# Step_Driver.net
KiCad netlist of a schematic drawn in Altium Designer
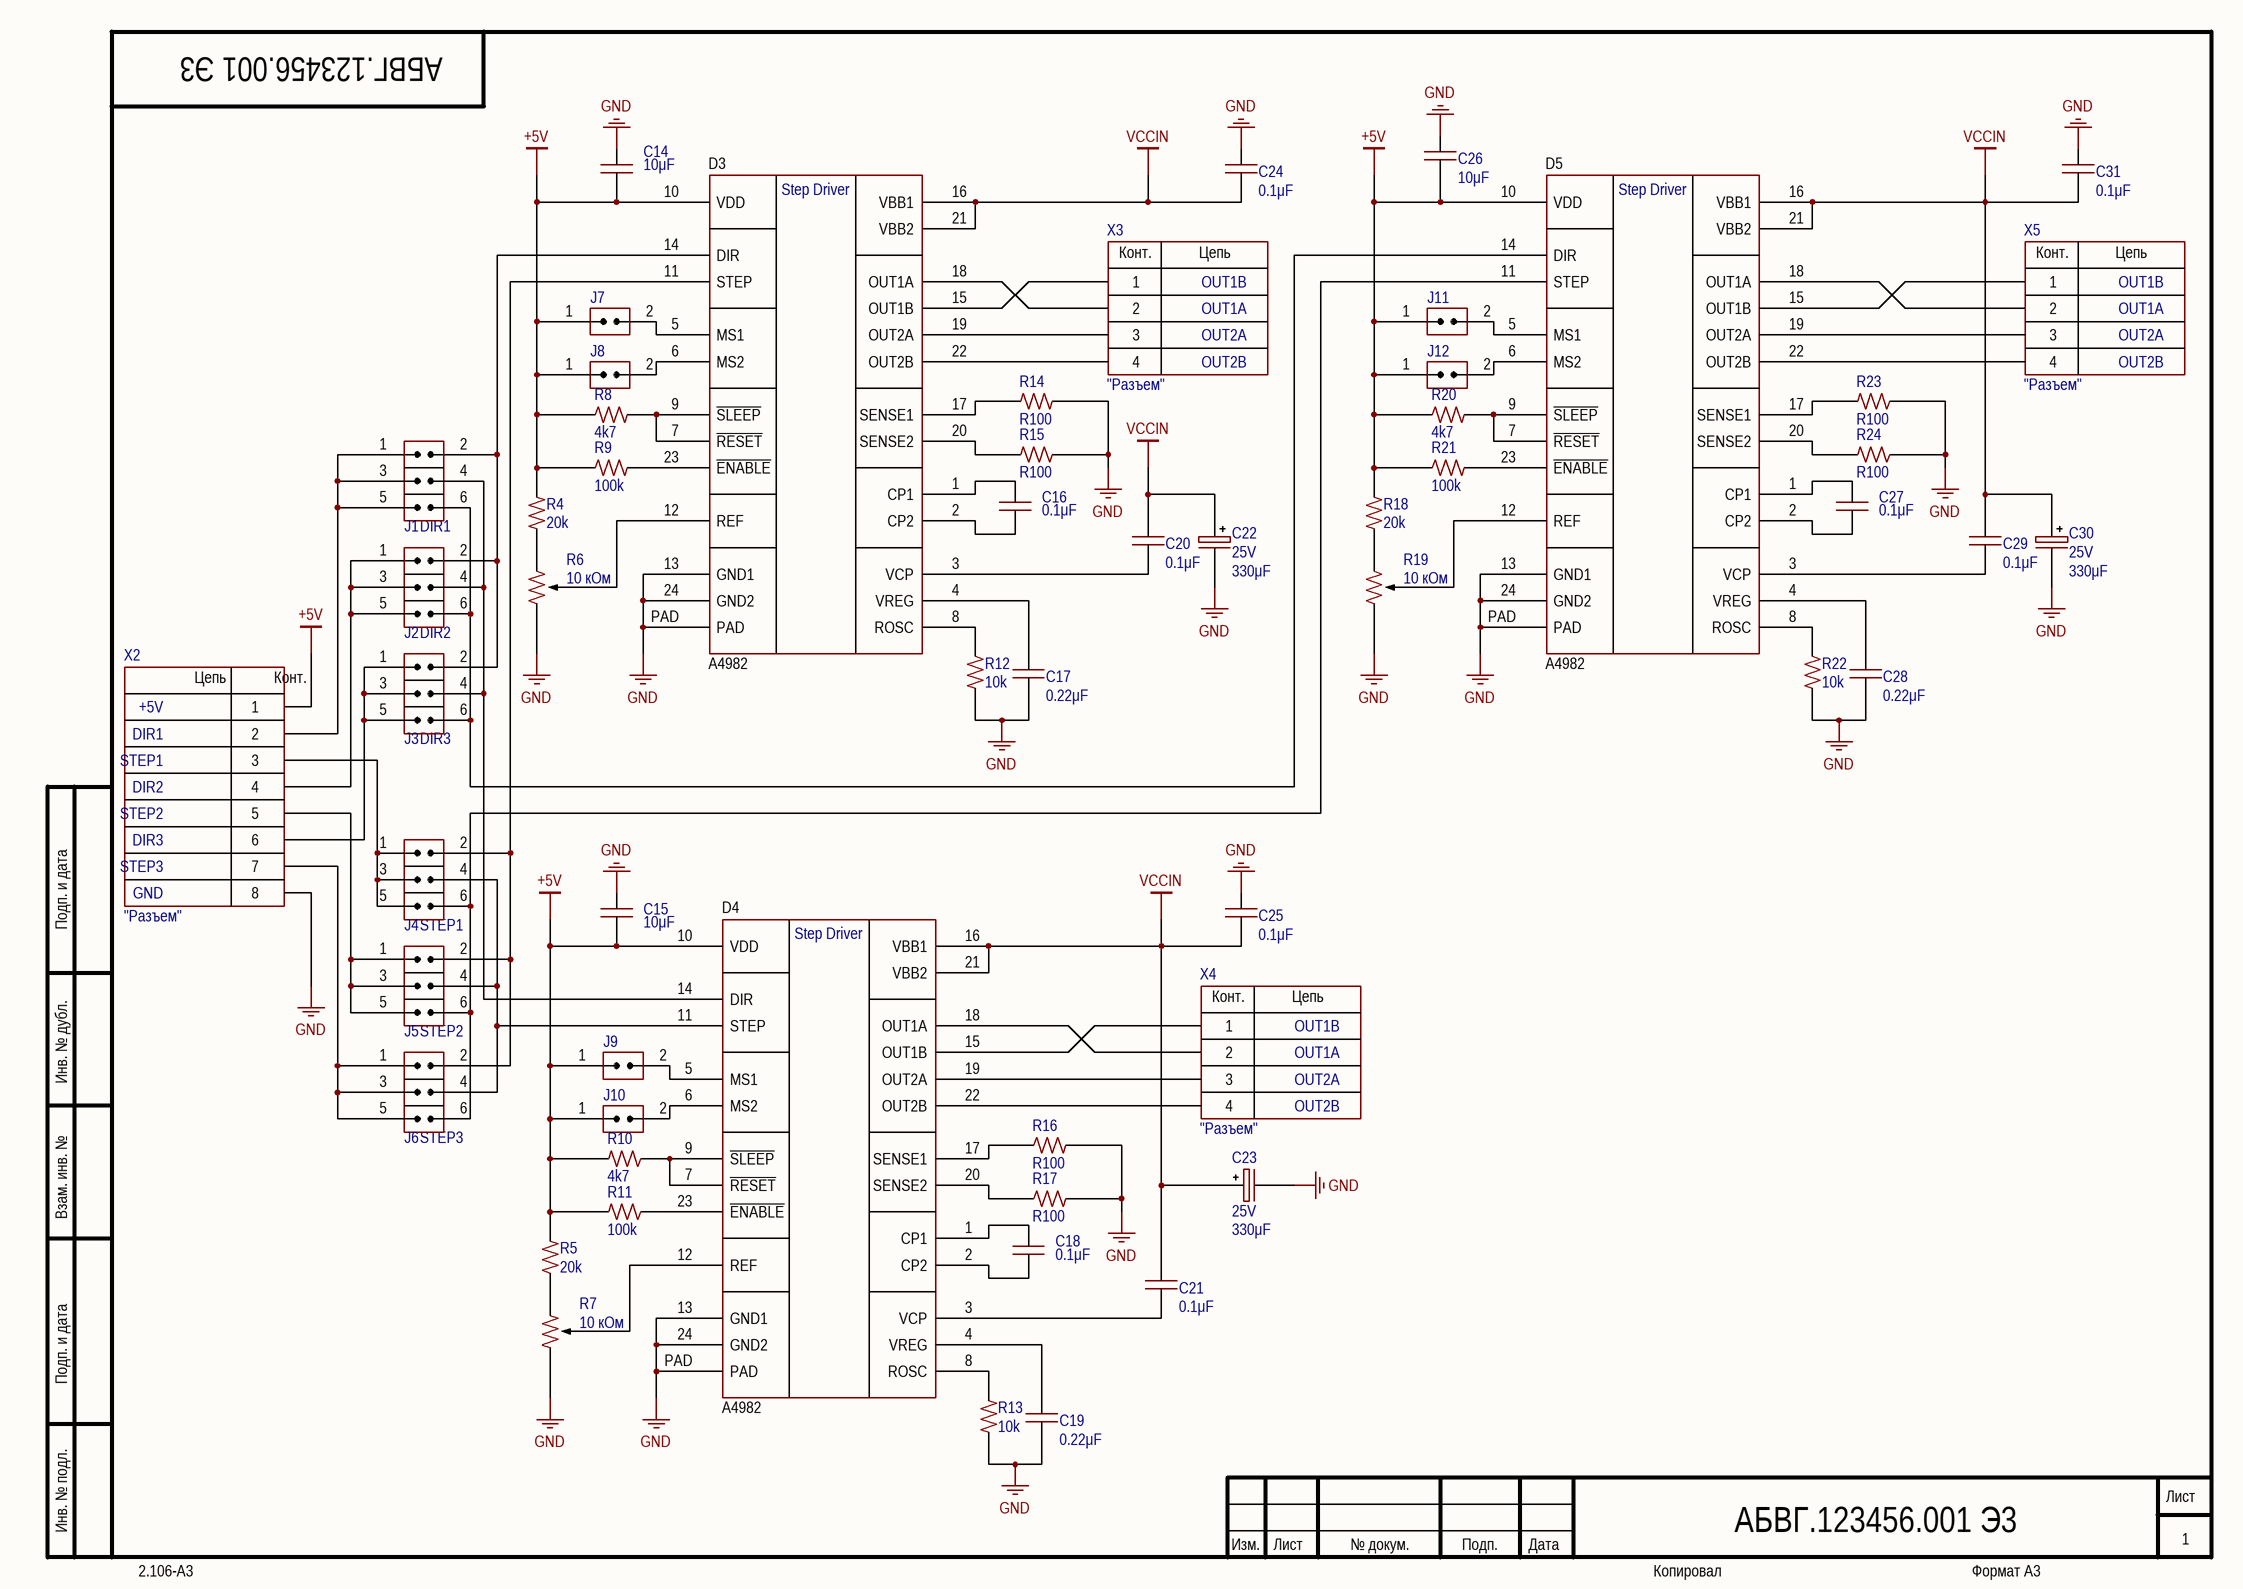
[diagram p0: Step_Driver.SchDoc]

(export (version "E")
  (design (tool "Eeschema 10.0.6"))
  (components
    (comp (ref "C14")
      (value "Керамический SMD")
      (footprint "Standart_Case:CAP: 0805")
      (fields (field (name "ЗНАЧЕНИЕ") "10μF"))
      (libsource (lib "Capacitor") (part "Керамический SMD"))
    )
    (comp (ref "C15")
      (value "Керамический SMD")
      (footprint "Standart_Case:CAP: 0805")
      (fields (field (name "ЗНАЧЕНИЕ") "10μF"))
      (libsource (lib "Capacitor") (part "Керамический SMD"))
    )
    (comp (ref "C16")
      (value "Керамический SMD")
      (footprint "Standart_Case:CAP: 0805")
      (fields (field (name "ЗНАЧЕНИЕ") "0.1μF"))
      (libsource (lib "Capacitor") (part "Керамический SMD"))
    )
    (comp (ref "C17")
      (value "Керамический SMD")
      (footprint "Standart_Case:CAP: 0805")
      (fields (field (name "ЗНАЧЕНИЕ") "0.22μF"))
      (libsource (lib "Capacitor") (part "Керамический SMD"))
    )
    (comp (ref "C18")
      (value "Керамический SMD")
      (footprint "Standart_Case:CAP: 0805")
      (fields (field (name "ЗНАЧЕНИЕ") "0.1μF"))
      (libsource (lib "Capacitor") (part "Керамический SMD"))
    )
    (comp (ref "C19")
      (value "Керамический SMD")
      (footprint "Standart_Case:CAP: 0805")
      (fields (field (name "ЗНАЧЕНИЕ") "0.22μF"))
      (libsource (lib "Capacitor") (part "Керамический SMD"))
    )
    (comp (ref "C20")
      (value "Керамический SMD")
      (footprint "Standart_Case:CAP: 0805")
      (fields (field (name "ЗНАЧЕНИЕ") "0.1μF"))
      (libsource (lib "Capacitor") (part "Керамический SMD"))
    )
    (comp (ref "C21")
      (value "Керамический SMD")
      (footprint "Standart_Case:CAP: 0805")
      (fields (field (name "ЗНАЧЕНИЕ") "0.1μF"))
      (libsource (lib "Capacitor") (part "Керамический SMD"))
    )
    (comp (ref "C22")
      (value "~")
      (footprint "Custom_Case:CAP: SMD D6.3A6.6H7.7")
      (fields (field (name "НАПРЯЖЕНИЕ") "25V") (field (name "ЗНАЧЕНИЕ") "330μF"))
      (libsource (lib "") (part "Алюминиевые_1"))
    )
    (comp (ref "C23")
      (value "~")
      (footprint "Custom_Case:CAP: SMD D6.3A6.6H7.7")
      (fields (field (name "НАПРЯЖЕНИЕ") "25V") (field (name "ЗНАЧЕНИЕ") "330μF"))
      (libsource (lib "Capacitor") (part "Алюминиевые"))
    )
    (comp (ref "C24")
      (value "Керамический SMD")
      (footprint "Standart_Case:CAP: 0805")
      (fields (field (name "ЗНАЧЕНИЕ") "0.1μF"))
      (libsource (lib "Capacitor") (part "Керамический SMD"))
    )
    (comp (ref "C25")
      (value "Керамический SMD")
      (footprint "Standart_Case:CAP: 0805")
      (fields (field (name "ЗНАЧЕНИЕ") "0.1μF"))
      (libsource (lib "Capacitor") (part "Керамический SMD"))
    )
    (comp (ref "C26")
      (value "Керамический SMD")
      (footprint "Standart_Case:CAP: 0805")
      (fields (field (name "ЗНАЧЕНИЕ") "10μF"))
      (libsource (lib "Capacitor") (part "Керамический SMD"))
    )
    (comp (ref "C27")
      (value "Керамический SMD")
      (footprint "Standart_Case:CAP: 0805")
      (fields (field (name "ЗНАЧЕНИЕ") "0.1μF"))
      (libsource (lib "Capacitor") (part "Керамический SMD"))
    )
    (comp (ref "C28")
      (value "Керамический SMD")
      (footprint "Standart_Case:CAP: 0805")
      (fields (field (name "ЗНАЧЕНИЕ") "0.22μF"))
      (libsource (lib "Capacitor") (part "Керамический SMD"))
    )
    (comp (ref "C29")
      (value "Керамический SMD")
      (footprint "Standart_Case:CAP: 0805")
      (fields (field (name "ЗНАЧЕНИЕ") "0.1μF"))
      (libsource (lib "Capacitor") (part "Керамический SMD"))
    )
    (comp (ref "C30")
      (value "~")
      (footprint "Custom_Case:CAP: SMD D6.3A6.6H7.7")
      (fields (field (name "НАПРЯЖЕНИЕ") "25V") (field (name "ЗНАЧЕНИЕ") "330μF"))
      (libsource (lib "") (part "Алюминиевые_1"))
    )
    (comp (ref "C31")
      (value "Керамический SMD")
      (footprint "Standart_Case:CAP: 0805")
      (fields (field (name "ЗНАЧЕНИЕ") "0.1μF"))
      (libsource (lib "Capacitor") (part "Керамический SMD"))
    )
    (comp (ref "D3")
      (value "A4982")
      (footprint "Standart_Case:24-TSSOP-PAD")
      (description "Драйвер шагового двигателя")
      (fields (field (name "УНИКАЛЬНЫЙНОМЕР") "A4982"))
      (libsource (lib "IC_Other") (part "A4982"))
    )
    (comp (ref "D4")
      (value "A4982")
      (footprint "Standart_Case:24-TSSOP-PAD")
      (description "Драйвер шагового двигателя")
      (fields (field (name "УНИКАЛЬНЫЙНОМЕР") "A4982"))
      (libsource (lib "IC_Other") (part "A4982"))
    )
    (comp (ref "D5")
      (value "A4982")
      (footprint "Standart_Case:24-TSSOP-PAD")
      (description "Драйвер шагового двигателя")
      (fields (field (name "УНИКАЛЬНЫЙНОМЕР") "A4982"))
      (libsource (lib "IC_Other") (part "A4982"))
    )
    (comp (ref "J1")
      (value "~")
      (footprint "Custom_Case:CON: JUMPER x3")
      (fields (field (name "COMMENTTEXT") "DIR1"))
      (libsource (lib "Connector") (part "Jumper_6_pin"))
    )
    (comp (ref "J2")
      (value "~")
      (footprint "Custom_Case:CON: JUMPER x3")
      (fields (field (name "COMMENTTEXT") "DIR2"))
      (libsource (lib "Connector") (part "Jumper_6_pin"))
    )
    (comp (ref "J3")
      (value "~")
      (footprint "Custom_Case:CON: JUMPER x3")
      (fields (field (name "COMMENTTEXT") "DIR3"))
      (libsource (lib "Connector") (part "Jumper_6_pin"))
    )
    (comp (ref "J4")
      (value "~")
      (footprint "Custom_Case:CON: JUMPER x3")
      (fields (field (name "COMMENTTEXT") "STEP1"))
      (libsource (lib "Connector") (part "Jumper_6_pin"))
    )
    (comp (ref "J5")
      (value "~")
      (footprint "Custom_Case:CON: JUMPER x3")
      (fields (field (name "COMMENTTEXT") "STEP2"))
      (libsource (lib "Connector") (part "Jumper_6_pin"))
    )
    (comp (ref "J6")
      (value "~")
      (footprint "Custom_Case:CON: JUMPER x3")
      (fields (field (name "COMMENTTEXT") "STEP3"))
      (libsource (lib "Connector") (part "Jumper_6_pin"))
    )
    (comp (ref "J7")
      (value "~")
      (footprint "Custom_Case:CON: JUMPER x1")
      (libsource (lib "Connector") (part "Jumper_2_pin"))
    )
    (comp (ref "J8")
      (value "~")
      (footprint "Custom_Case:CON: JUMPER x1")
      (libsource (lib "Connector") (part "Jumper_2_pin"))
    )
    (comp (ref "J9")
      (value "~")
      (footprint "Custom_Case:CON: JUMPER x1")
      (libsource (lib "Connector") (part "Jumper_2_pin"))
    )
    (comp (ref "J10")
      (value "~")
      (footprint "Custom_Case:CON: JUMPER x1")
      (libsource (lib "Connector") (part "Jumper_2_pin"))
    )
    (comp (ref "J11")
      (value "~")
      (footprint "Custom_Case:CON: JUMPER x1")
      (libsource (lib "Connector") (part "Jumper_2_pin"))
    )
    (comp (ref "J12")
      (value "~")
      (footprint "Custom_Case:CON: JUMPER x1")
      (libsource (lib "Connector") (part "Jumper_2_pin"))
    )
    (comp (ref "R4")
      (value "Резистор SMD")
      (footprint "Standart_Case:RES: 0805")
      (fields (field (name "ЗНАЧЕНИЕ") "20k"))
      (libsource (lib "Resistor") (part "Резистор SMD"))
    )
    (comp (ref "R5")
      (value "Резистор SMD")
      (footprint "Standart_Case:RES: 0805")
      (fields (field (name "ЗНАЧЕНИЕ") "20k"))
      (libsource (lib "Resistor") (part "Резистор SMD"))
    )
    (comp (ref "R6")
      (value "Резистор подстроечный")
      (footprint "Custom_Case:RES: 3296W")
      (fields (field (name "ЗНАЧЕНИЕ") "10 кОм"))
      (libsource (lib "Resistor") (part "Резистор подстроечный"))
    )
    (comp (ref "R7")
      (value "Резистор подстроечный")
      (footprint "Custom_Case:RES: 3296W")
      (fields (field (name "ЗНАЧЕНИЕ") "10 кОм"))
      (libsource (lib "Resistor") (part "Резистор подстроечный"))
    )
    (comp (ref "R8")
      (value "Резистор SMD")
      (footprint "Standart_Case:RES: 0805")
      (fields (field (name "ЗНАЧЕНИЕ") "4k7"))
      (libsource (lib "Resistor") (part "Резистор SMD"))
    )
    (comp (ref "R9")
      (value "Резистор SMD")
      (footprint "Standart_Case:RES: 0805")
      (fields (field (name "ЗНАЧЕНИЕ") "100k"))
      (libsource (lib "Resistor") (part "Резистор SMD"))
    )
    (comp (ref "R10")
      (value "Резистор SMD")
      (footprint "Standart_Case:RES: 0805")
      (fields (field (name "ЗНАЧЕНИЕ") "4k7"))
      (libsource (lib "Resistor") (part "Резистор SMD"))
    )
    (comp (ref "R11")
      (value "Резистор SMD")
      (footprint "Standart_Case:RES: 0805")
      (fields (field (name "ЗНАЧЕНИЕ") "100k"))
      (libsource (lib "Resistor") (part "Резистор SMD"))
    )
    (comp (ref "R12")
      (value "Резистор SMD")
      (footprint "Standart_Case:RES: 0805")
      (fields (field (name "ЗНАЧЕНИЕ") "10k"))
      (libsource (lib "Resistor") (part "Резистор SMD"))
    )
    (comp (ref "R13")
      (value "Резистор SMD")
      (footprint "Standart_Case:RES: 0805")
      (fields (field (name "ЗНАЧЕНИЕ") "10k"))
      (libsource (lib "Resistor") (part "Резистор SMD"))
    )
    (comp (ref "R14")
      (value "Резистор SMD")
      (footprint "Standart_Case:RES: 2010")
      (fields (field (name "ЗНАЧЕНИЕ") "R100"))
      (libsource (lib "Resistor") (part "Резистор SMD"))
    )
    (comp (ref "R15")
      (value "Резистор SMD")
      (footprint "Standart_Case:RES: 2010")
      (fields (field (name "ЗНАЧЕНИЕ") "R100"))
      (libsource (lib "Resistor") (part "Резистор SMD"))
    )
    (comp (ref "R16")
      (value "Резистор SMD")
      (footprint "Standart_Case:RES: 2010")
      (fields (field (name "ЗНАЧЕНИЕ") "R100"))
      (libsource (lib "Resistor") (part "Резистор SMD"))
    )
    (comp (ref "R17")
      (value "Резистор SMD")
      (footprint "Standart_Case:RES: 2010")
      (fields (field (name "ЗНАЧЕНИЕ") "R100"))
      (libsource (lib "Resistor") (part "Резистор SMD"))
    )
    (comp (ref "R18")
      (value "Резистор SMD")
      (footprint "Standart_Case:RES: 0805")
      (fields (field (name "ЗНАЧЕНИЕ") "20k"))
      (libsource (lib "Resistor") (part "Резистор SMD"))
    )
    (comp (ref "R19")
      (value "Резистор подстроечный")
      (footprint "Custom_Case:RES: 3296W")
      (fields (field (name "ЗНАЧЕНИЕ") "10 кОм"))
      (libsource (lib "Resistor") (part "Резистор подстроечный"))
    )
    (comp (ref "R20")
      (value "Резистор SMD")
      (footprint "Standart_Case:RES: 0805")
      (fields (field (name "ЗНАЧЕНИЕ") "4k7"))
      (libsource (lib "Resistor") (part "Резистор SMD"))
    )
    (comp (ref "R21")
      (value "Резистор SMD")
      (footprint "Standart_Case:RES: 0805")
      (fields (field (name "ЗНАЧЕНИЕ") "100k"))
      (libsource (lib "Resistor") (part "Резистор SMD"))
    )
    (comp (ref "R22")
      (value "Резистор SMD")
      (footprint "Standart_Case:RES: 0805")
      (fields (field (name "ЗНАЧЕНИЕ") "10k"))
      (libsource (lib "Resistor") (part "Резистор SMD"))
    )
    (comp (ref "R23")
      (value "Резистор SMD")
      (footprint "Standart_Case:RES: 2010")
      (fields (field (name "ЗНАЧЕНИЕ") "R100"))
      (libsource (lib "Resistor") (part "Резистор SMD"))
    )
    (comp (ref "R24")
      (value "Резистор SMD")
      (footprint "Standart_Case:RES: 2010")
      (fields (field (name "ЗНАЧЕНИЕ") "R100"))
      (libsource (lib "Resistor") (part "Резистор SMD"))
    )
    (comp (ref "X2")
      (value "~")
      (footprint "Custom_Case:CON: PLS-8")
      (fields
        (field (name "MANUFACTURER") "Connfly")
        (field (name "VALUEMANUFACTURERPARTNUMBER") "Connector, 8pin, 2.54mm, 500VAC, 3A")
        (field (name "PARTNUMBER") "PLS-8")
        (field (name "COMMENTTEXT") "\"Разъем\"")
      )
      (libsource (lib "Connector") (part "PLS-8"))
    )
    (comp (ref "X3")
      (value "~")
      (footprint "Custom_Case:CON: 15EDGVC-3.5-04")
      (fields
        (field (name "MANUFACTURER") "Degson")
        (field (name "VALUEMANUFACTURERPARTNUMBER") "Terminal connector, 6pin, 3.5mm, 300VAC, 10A")
        (field (name "PARTNUMBER") "DG350-3.5-06P-14")
        (field (name "COMMENTTEXT") "\"Разъем\"")
      )
      (libsource (lib "Connector") (part "Connector_terminal_4pin"))
    )
    (comp (ref "X4")
      (value "~")
      (footprint "Custom_Case:CON: 15EDGVC-3.5-04")
      (fields
        (field (name "MANUFACTURER") "Degson")
        (field (name "VALUEMANUFACTURERPARTNUMBER") "Terminal connector, 6pin, 3.5mm, 300VAC, 10A")
        (field (name "PARTNUMBER") "DG350-3.5-06P-14")
        (field (name "COMMENTTEXT") "\"Разъем\"")
      )
      (libsource (lib "Connector") (part "Connector_terminal_4pin"))
    )
    (comp (ref "X5")
      (value "~")
      (footprint "Custom_Case:CON: 15EDGVC-3.5-04")
      (fields
        (field (name "MANUFACTURER") "Degson")
        (field (name "VALUEMANUFACTURERPARTNUMBER") "Terminal connector, 6pin, 3.5mm, 300VAC, 10A")
        (field (name "PARTNUMBER") "DG350-3.5-06P-14")
        (field (name "COMMENTTEXT") "\"Разъем\"")
      )
      (libsource (lib "Connector") (part "Connector_terminal_4pin"))
    )
  )
  (nets
    (net (code "1") (name "+5V") (class "Default")
      (node (ref "C14") (pin "1") (pinfunction "1_1") (pintype "passive"))
      (node (ref "C15") (pin "1") (pinfunction "1_1") (pintype "passive"))
      (node (ref "C26") (pin "1") (pinfunction "1_1") (pintype "passive"))
      (node (ref "D3") (pin "10") (pinfunction "VDD_10") (pintype "passive"))
      (node (ref "D4") (pin "10") (pinfunction "VDD_10") (pintype "passive"))
      (node (ref "D5") (pin "10") (pinfunction "VDD_10") (pintype "passive"))
      (node (ref "J10") (pin "1") (pinfunction "IN_1") (pintype "passive"))
      (node (ref "J11") (pin "1") (pinfunction "IN_1") (pintype "passive"))
      (node (ref "J12") (pin "1") (pinfunction "IN_1") (pintype "passive"))
      (node (ref "J7") (pin "1") (pinfunction "IN_1") (pintype "passive"))
      (node (ref "J8") (pin "1") (pinfunction "IN_1") (pintype "passive"))
      (node (ref "J9") (pin "1") (pinfunction "IN_1") (pintype "passive"))
      (node (ref "R10") (pin "1") (pinfunction "1_1") (pintype "passive"))
      (node (ref "R11") (pin "1") (pinfunction "1_1") (pintype "passive"))
      (node (ref "R18") (pin "2") (pinfunction "2_2") (pintype "passive"))
      (node (ref "R20") (pin "1") (pinfunction "1_1") (pintype "passive"))
      (node (ref "R21") (pin "1") (pinfunction "1_1") (pintype "passive"))
      (node (ref "R4") (pin "2") (pinfunction "2_2") (pintype "passive"))
      (node (ref "R5") (pin "2") (pinfunction "2_2") (pintype "passive"))
      (node (ref "R8") (pin "1") (pinfunction "1_1") (pintype "passive"))
      (node (ref "R9") (pin "1") (pinfunction "1_1") (pintype "passive"))
      (node (ref "X2") (pin "1") (pinfunction "1_1") (pintype "passive"))
    )
    (net (code "2") (name "GND") (class "Default")
      (node (ref "C14") (pin "2") (pinfunction "2_2") (pintype "passive"))
      (node (ref "C15") (pin "2") (pinfunction "2_2") (pintype "passive"))
      (node (ref "C17") (pin "1") (pinfunction "1_1") (pintype "passive"))
      (node (ref "C19") (pin "1") (pinfunction "1_1") (pintype "passive"))
      (node (ref "C22") (pin "2") (pinfunction "2_2") (pintype "passive"))
      (node (ref "C23") (pin "2") (pinfunction "2_2") (pintype "passive"))
      (node (ref "C24") (pin "1") (pinfunction "1_1") (pintype "passive"))
      (node (ref "C25") (pin "1") (pinfunction "1_1") (pintype "passive"))
      (node (ref "C26") (pin "2") (pinfunction "2_2") (pintype "passive"))
      (node (ref "C28") (pin "1") (pinfunction "1_1") (pintype "passive"))
      (node (ref "C30") (pin "2") (pinfunction "2_2") (pintype "passive"))
      (node (ref "C31") (pin "1") (pinfunction "1_1") (pintype "passive"))
      (node (ref "D3") (pin "13") (pinfunction "GND1_13") (pintype "passive"))
      (node (ref "D3") (pin "24") (pinfunction "GND2_24") (pintype "passive"))
      (node (ref "D3") (pin "PAD") (pinfunction "PAD_PAD") (pintype "passive"))
      (node (ref "D4") (pin "13") (pinfunction "GND1_13") (pintype "passive"))
      (node (ref "D4") (pin "24") (pinfunction "GND2_24") (pintype "passive"))
      (node (ref "D4") (pin "PAD") (pinfunction "PAD_PAD") (pintype "passive"))
      (node (ref "D5") (pin "13") (pinfunction "GND1_13") (pintype "passive"))
      (node (ref "D5") (pin "24") (pinfunction "GND2_24") (pintype "passive"))
      (node (ref "D5") (pin "PAD") (pinfunction "PAD_PAD") (pintype "passive"))
      (node (ref "R12") (pin "1") (pinfunction "1_1") (pintype "passive"))
      (node (ref "R13") (pin "1") (pinfunction "1_1") (pintype "passive"))
      (node (ref "R14") (pin "2") (pinfunction "2_2") (pintype "passive"))
      (node (ref "R15") (pin "2") (pinfunction "2_2") (pintype "passive"))
      (node (ref "R16") (pin "2") (pinfunction "2_2") (pintype "passive"))
      (node (ref "R17") (pin "2") (pinfunction "2_2") (pintype "passive"))
      (node (ref "R19") (pin "3") (pinfunction "3_3") (pintype "passive"))
      (node (ref "R22") (pin "1") (pinfunction "1_1") (pintype "passive"))
      (node (ref "R23") (pin "2") (pinfunction "2_2") (pintype "passive"))
      (node (ref "R24") (pin "2") (pinfunction "2_2") (pintype "passive"))
      (node (ref "R6") (pin "3") (pinfunction "3_3") (pintype "passive"))
      (node (ref "R7") (pin "3") (pinfunction "3_3") (pintype "passive"))
      (node (ref "X2") (pin "8") (pinfunction "8_8") (pintype "power_in"))
    )
    (net (code "3") (name "Net-(D3-CP1)") (class "Default")
      (node (ref "C16") (pin "2") (pinfunction "2_2") (pintype "passive"))
      (node (ref "D3") (pin "1") (pinfunction "CP1_1") (pintype "passive"))
    )
    (net (code "4") (name "Net-(D3-CP2)") (class "Default")
      (node (ref "C16") (pin "1") (pinfunction "1_1") (pintype "passive"))
      (node (ref "D3") (pin "2") (pinfunction "CP2_2") (pintype "passive"))
    )
    (net (code "5") (name "Net-(D3-DIR)") (class "Default")
      (node (ref "D3") (pin "14") (pinfunction "DIR_14") (pintype "passive"))
      (node (ref "J1") (pin "2") (pinfunction "IN_2") (pintype "passive"))
      (node (ref "J2") (pin "2") (pinfunction "IN_2") (pintype "passive"))
      (node (ref "J3") (pin "2") (pinfunction "IN_2") (pintype "passive"))
    )
    (net (code "6") (name "Net-(D3-MS1)") (class "Default")
      (node (ref "D3") (pin "5") (pinfunction "MS1_5") (pintype "passive"))
      (node (ref "J7") (pin "2") (pinfunction "IN_2") (pintype "passive"))
    )
    (net (code "7") (name "Net-(D3-MS2)") (class "Default")
      (node (ref "D3") (pin "6") (pinfunction "MS2_6") (pintype "passive"))
      (node (ref "J8") (pin "2") (pinfunction "IN_2") (pintype "passive"))
    )
    (net (code "8") (name "Net-(D3-OUT1A)") (class "Default")
      (node (ref "D3") (pin "18") (pinfunction "OUT1A_18") (pintype "passive"))
      (node (ref "X3") (pin "2") (pinfunction "2_2") (pintype "passive"))
    )
    (net (code "9") (name "Net-(D3-OUT1B)") (class "Default")
      (node (ref "D3") (pin "15") (pinfunction "OUT1B_15") (pintype "passive"))
      (node (ref "X3") (pin "1") (pinfunction "1_1") (pintype "passive"))
    )
    (net (code "10") (name "Net-(D3-OUT2A)") (class "Default")
      (node (ref "D3") (pin "19") (pinfunction "OUT2A_19") (pintype "passive"))
      (node (ref "X3") (pin "3") (pinfunction "3_3") (pintype "power_in"))
    )
    (net (code "11") (name "Net-(D3-OUT2B)") (class "Default")
      (node (ref "D3") (pin "22") (pinfunction "OUT2B_22") (pintype "passive"))
      (node (ref "X3") (pin "4") (pinfunction "4_4") (pintype "power_in"))
    )
    (net (code "12") (name "Net-(D3-REF)") (class "Default")
      (node (ref "D3") (pin "12") (pinfunction "REF_12") (pintype "passive"))
      (node (ref "R6") (pin "2") (pinfunction "2_2") (pintype "passive"))
    )
    (net (code "13") (name "Net-(D3-ROSC)") (class "Default")
      (node (ref "D3") (pin "8") (pinfunction "ROSC_8") (pintype "passive"))
      (node (ref "R12") (pin "2") (pinfunction "2_2") (pintype "passive"))
    )
    (net (code "14") (name "Net-(D3-SENSE1)") (class "Default")
      (node (ref "D3") (pin "17") (pinfunction "SENSE1_17") (pintype "passive"))
      (node (ref "R14") (pin "1") (pinfunction "1_1") (pintype "passive"))
    )
    (net (code "15") (name "Net-(D3-SENSE2)") (class "Default")
      (node (ref "D3") (pin "20") (pinfunction "SENSE2_20") (pintype "passive"))
      (node (ref "R15") (pin "1") (pinfunction "1_1") (pintype "passive"))
    )
    (net (code "16") (name "Net-(D3-STEP)") (class "Default")
      (node (ref "D3") (pin "11") (pinfunction "STEP_11") (pintype "passive"))
      (node (ref "J4") (pin "2") (pinfunction "IN_2") (pintype "passive"))
      (node (ref "J5") (pin "2") (pinfunction "IN_2") (pintype "passive"))
      (node (ref "J6") (pin "2") (pinfunction "IN_2") (pintype "passive"))
    )
    (net (code "17") (name "Net-(D3-VCP)") (class "Default")
      (node (ref "C20") (pin "1") (pinfunction "1_1") (pintype "passive"))
      (node (ref "D3") (pin "3") (pinfunction "VCP_3") (pintype "passive"))
    )
    (net (code "18") (name "Net-(D3-VREG)") (class "Default")
      (node (ref "C17") (pin "2") (pinfunction "2_2") (pintype "passive"))
      (node (ref "D3") (pin "4") (pinfunction "VREG_4") (pintype "passive"))
    )
    (net (code "19") (name "Net-(D3-~{ENABLE})") (class "Default")
      (node (ref "D3") (pin "23") (pinfunction "~{ENABLE}_23") (pintype "power_in"))
      (node (ref "R9") (pin "2") (pinfunction "2_2") (pintype "passive"))
    )
    (net (code "20") (name "Net-(D3-~{RESET})") (class "Default")
      (node (ref "D3") (pin "7") (pinfunction "~{RESET}_7") (pintype "power_in"))
      (node (ref "D3") (pin "9") (pinfunction "~{SLEEP}_9") (pintype "passive"))
      (node (ref "R8") (pin "2") (pinfunction "2_2") (pintype "passive"))
    )
    (net (code "21") (name "Net-(D4-CP1)") (class "Default")
      (node (ref "C18") (pin "2") (pinfunction "2_2") (pintype "passive"))
      (node (ref "D4") (pin "1") (pinfunction "CP1_1") (pintype "passive"))
    )
    (net (code "22") (name "Net-(D4-CP2)") (class "Default")
      (node (ref "C18") (pin "1") (pinfunction "1_1") (pintype "passive"))
      (node (ref "D4") (pin "2") (pinfunction "CP2_2") (pintype "passive"))
    )
    (net (code "23") (name "Net-(D4-DIR)") (class "Default")
      (node (ref "D4") (pin "14") (pinfunction "DIR_14") (pintype "passive"))
      (node (ref "J1") (pin "4") (pinfunction "IN_4") (pintype "passive"))
      (node (ref "J2") (pin "4") (pinfunction "IN_4") (pintype "passive"))
      (node (ref "J3") (pin "4") (pinfunction "IN_4") (pintype "passive"))
    )
    (net (code "24") (name "Net-(D4-MS1)") (class "Default")
      (node (ref "D4") (pin "5") (pinfunction "MS1_5") (pintype "passive"))
      (node (ref "J9") (pin "2") (pinfunction "IN_2") (pintype "passive"))
    )
    (net (code "25") (name "Net-(D4-MS2)") (class "Default")
      (node (ref "D4") (pin "6") (pinfunction "MS2_6") (pintype "passive"))
      (node (ref "J10") (pin "2") (pinfunction "IN_2") (pintype "passive"))
    )
    (net (code "26") (name "Net-(D4-OUT1A)") (class "Default")
      (node (ref "D4") (pin "18") (pinfunction "OUT1A_18") (pintype "passive"))
      (node (ref "X4") (pin "2") (pinfunction "2_2") (pintype "passive"))
    )
    (net (code "27") (name "Net-(D4-OUT1B)") (class "Default")
      (node (ref "D4") (pin "15") (pinfunction "OUT1B_15") (pintype "passive"))
      (node (ref "X4") (pin "1") (pinfunction "1_1") (pintype "passive"))
    )
    (net (code "28") (name "Net-(D4-OUT2A)") (class "Default")
      (node (ref "D4") (pin "19") (pinfunction "OUT2A_19") (pintype "passive"))
      (node (ref "X4") (pin "3") (pinfunction "3_3") (pintype "power_in"))
    )
    (net (code "29") (name "Net-(D4-OUT2B)") (class "Default")
      (node (ref "D4") (pin "22") (pinfunction "OUT2B_22") (pintype "passive"))
      (node (ref "X4") (pin "4") (pinfunction "4_4") (pintype "power_in"))
    )
    (net (code "30") (name "Net-(D4-REF)") (class "Default")
      (node (ref "D4") (pin "12") (pinfunction "REF_12") (pintype "passive"))
      (node (ref "R7") (pin "2") (pinfunction "2_2") (pintype "passive"))
    )
    (net (code "31") (name "Net-(D4-ROSC)") (class "Default")
      (node (ref "D4") (pin "8") (pinfunction "ROSC_8") (pintype "passive"))
      (node (ref "R13") (pin "2") (pinfunction "2_2") (pintype "passive"))
    )
    (net (code "32") (name "Net-(D4-SENSE1)") (class "Default")
      (node (ref "D4") (pin "17") (pinfunction "SENSE1_17") (pintype "passive"))
      (node (ref "R16") (pin "1") (pinfunction "1_1") (pintype "passive"))
    )
    (net (code "33") (name "Net-(D4-SENSE2)") (class "Default")
      (node (ref "D4") (pin "20") (pinfunction "SENSE2_20") (pintype "passive"))
      (node (ref "R17") (pin "1") (pinfunction "1_1") (pintype "passive"))
    )
    (net (code "34") (name "Net-(D4-STEP)") (class "Default")
      (node (ref "D4") (pin "11") (pinfunction "STEP_11") (pintype "passive"))
      (node (ref "J4") (pin "4") (pinfunction "IN_4") (pintype "passive"))
      (node (ref "J5") (pin "4") (pinfunction "IN_4") (pintype "passive"))
      (node (ref "J6") (pin "4") (pinfunction "IN_4") (pintype "passive"))
    )
    (net (code "35") (name "Net-(D4-VCP)") (class "Default")
      (node (ref "C21") (pin "1") (pinfunction "1_1") (pintype "passive"))
      (node (ref "D4") (pin "3") (pinfunction "VCP_3") (pintype "passive"))
    )
    (net (code "36") (name "Net-(D4-VREG)") (class "Default")
      (node (ref "C19") (pin "2") (pinfunction "2_2") (pintype "passive"))
      (node (ref "D4") (pin "4") (pinfunction "VREG_4") (pintype "passive"))
    )
    (net (code "37") (name "Net-(D4-~{ENABLE})") (class "Default")
      (node (ref "D4") (pin "23") (pinfunction "~{ENABLE}_23") (pintype "power_in"))
      (node (ref "R11") (pin "2") (pinfunction "2_2") (pintype "passive"))
    )
    (net (code "38") (name "Net-(D4-~{RESET})") (class "Default")
      (node (ref "D4") (pin "7") (pinfunction "~{RESET}_7") (pintype "power_in"))
      (node (ref "D4") (pin "9") (pinfunction "~{SLEEP}_9") (pintype "passive"))
      (node (ref "R10") (pin "2") (pinfunction "2_2") (pintype "passive"))
    )
    (net (code "39") (name "Net-(D5-CP1)") (class "Default")
      (node (ref "C27") (pin "2") (pinfunction "2_2") (pintype "passive"))
      (node (ref "D5") (pin "1") (pinfunction "CP1_1") (pintype "passive"))
    )
    (net (code "40") (name "Net-(D5-CP2)") (class "Default")
      (node (ref "C27") (pin "1") (pinfunction "1_1") (pintype "passive"))
      (node (ref "D5") (pin "2") (pinfunction "CP2_2") (pintype "passive"))
    )
    (net (code "41") (name "Net-(D5-DIR)") (class "Default")
      (node (ref "D5") (pin "14") (pinfunction "DIR_14") (pintype "passive"))
      (node (ref "J1") (pin "6") (pinfunction "IN_6") (pintype "passive"))
      (node (ref "J2") (pin "6") (pinfunction "IN_6") (pintype "passive"))
      (node (ref "J3") (pin "6") (pinfunction "IN_6") (pintype "passive"))
    )
    (net (code "42") (name "Net-(D5-MS1)") (class "Default")
      (node (ref "D5") (pin "5") (pinfunction "MS1_5") (pintype "passive"))
      (node (ref "J11") (pin "2") (pinfunction "IN_2") (pintype "passive"))
    )
    (net (code "43") (name "Net-(D5-MS2)") (class "Default")
      (node (ref "D5") (pin "6") (pinfunction "MS2_6") (pintype "passive"))
      (node (ref "J12") (pin "2") (pinfunction "IN_2") (pintype "passive"))
    )
    (net (code "44") (name "Net-(D5-OUT1A)") (class "Default")
      (node (ref "D5") (pin "18") (pinfunction "OUT1A_18") (pintype "passive"))
      (node (ref "X5") (pin "2") (pinfunction "2_2") (pintype "passive"))
    )
    (net (code "45") (name "Net-(D5-OUT1B)") (class "Default")
      (node (ref "D5") (pin "15") (pinfunction "OUT1B_15") (pintype "passive"))
      (node (ref "X5") (pin "1") (pinfunction "1_1") (pintype "passive"))
    )
    (net (code "46") (name "Net-(D5-OUT2A)") (class "Default")
      (node (ref "D5") (pin "19") (pinfunction "OUT2A_19") (pintype "passive"))
      (node (ref "X5") (pin "3") (pinfunction "3_3") (pintype "power_in"))
    )
    (net (code "47") (name "Net-(D5-OUT2B)") (class "Default")
      (node (ref "D5") (pin "22") (pinfunction "OUT2B_22") (pintype "passive"))
      (node (ref "X5") (pin "4") (pinfunction "4_4") (pintype "power_in"))
    )
    (net (code "48") (name "Net-(D5-REF)") (class "Default")
      (node (ref "D5") (pin "12") (pinfunction "REF_12") (pintype "passive"))
      (node (ref "R19") (pin "2") (pinfunction "2_2") (pintype "passive"))
    )
    (net (code "49") (name "Net-(D5-ROSC)") (class "Default")
      (node (ref "D5") (pin "8") (pinfunction "ROSC_8") (pintype "passive"))
      (node (ref "R22") (pin "2") (pinfunction "2_2") (pintype "passive"))
    )
    (net (code "50") (name "Net-(D5-SENSE1)") (class "Default")
      (node (ref "D5") (pin "17") (pinfunction "SENSE1_17") (pintype "passive"))
      (node (ref "R23") (pin "1") (pinfunction "1_1") (pintype "passive"))
    )
    (net (code "51") (name "Net-(D5-SENSE2)") (class "Default")
      (node (ref "D5") (pin "20") (pinfunction "SENSE2_20") (pintype "passive"))
      (node (ref "R24") (pin "1") (pinfunction "1_1") (pintype "passive"))
    )
    (net (code "52") (name "Net-(D5-STEP)") (class "Default")
      (node (ref "D5") (pin "11") (pinfunction "STEP_11") (pintype "passive"))
      (node (ref "J4") (pin "6") (pinfunction "IN_6") (pintype "passive"))
      (node (ref "J5") (pin "6") (pinfunction "IN_6") (pintype "passive"))
      (node (ref "J6") (pin "6") (pinfunction "IN_6") (pintype "passive"))
    )
    (net (code "53") (name "Net-(D5-VCP)") (class "Default")
      (node (ref "C29") (pin "1") (pinfunction "1_1") (pintype "passive"))
      (node (ref "D5") (pin "3") (pinfunction "VCP_3") (pintype "passive"))
    )
    (net (code "54") (name "Net-(D5-VREG)") (class "Default")
      (node (ref "C28") (pin "2") (pinfunction "2_2") (pintype "passive"))
      (node (ref "D5") (pin "4") (pinfunction "VREG_4") (pintype "passive"))
    )
    (net (code "55") (name "Net-(D5-~{ENABLE})") (class "Default")
      (node (ref "D5") (pin "23") (pinfunction "~{ENABLE}_23") (pintype "power_in"))
      (node (ref "R21") (pin "2") (pinfunction "2_2") (pintype "passive"))
    )
    (net (code "56") (name "Net-(D5-~{RESET})") (class "Default")
      (node (ref "D5") (pin "7") (pinfunction "~{RESET}_7") (pintype "power_in"))
      (node (ref "D5") (pin "9") (pinfunction "~{SLEEP}_9") (pintype "passive"))
      (node (ref "R20") (pin "2") (pinfunction "2_2") (pintype "passive"))
    )
    (net (code "57") (name "Net-(J1-IN-Pad1)") (class "Default")
      (node (ref "J1") (pin "1") (pinfunction "IN_1") (pintype "passive"))
      (node (ref "J1") (pin "3") (pinfunction "IN_3") (pintype "passive"))
      (node (ref "J1") (pin "5") (pinfunction "IN_5") (pintype "passive"))
      (node (ref "X2") (pin "2") (pinfunction "2_2") (pintype "passive"))
    )
    (net (code "58") (name "Net-(J2-IN-Pad1)") (class "Default")
      (node (ref "J2") (pin "1") (pinfunction "IN_1") (pintype "passive"))
      (node (ref "J2") (pin "3") (pinfunction "IN_3") (pintype "passive"))
      (node (ref "J2") (pin "5") (pinfunction "IN_5") (pintype "passive"))
      (node (ref "X2") (pin "4") (pinfunction "4_4") (pintype "power_in"))
    )
    (net (code "59") (name "Net-(J3-IN-Pad1)") (class "Default")
      (node (ref "J3") (pin "1") (pinfunction "IN_1") (pintype "passive"))
      (node (ref "J3") (pin "3") (pinfunction "IN_3") (pintype "passive"))
      (node (ref "J3") (pin "5") (pinfunction "IN_5") (pintype "passive"))
      (node (ref "X2") (pin "6") (pinfunction "6_6") (pintype "power_in"))
    )
    (net (code "60") (name "Net-(J4-IN-Pad1)") (class "Default")
      (node (ref "J4") (pin "1") (pinfunction "IN_1") (pintype "passive"))
      (node (ref "J4") (pin "3") (pinfunction "IN_3") (pintype "passive"))
      (node (ref "J4") (pin "5") (pinfunction "IN_5") (pintype "passive"))
      (node (ref "X2") (pin "3") (pinfunction "3_3") (pintype "power_in"))
    )
    (net (code "61") (name "Net-(J5-IN-Pad1)") (class "Default")
      (node (ref "J5") (pin "1") (pinfunction "IN_1") (pintype "passive"))
      (node (ref "J5") (pin "3") (pinfunction "IN_3") (pintype "passive"))
      (node (ref "J5") (pin "5") (pinfunction "IN_5") (pintype "passive"))
      (node (ref "X2") (pin "5") (pinfunction "5_5") (pintype "power_in"))
    )
    (net (code "62") (name "Net-(J6-IN-Pad1)") (class "Default")
      (node (ref "J6") (pin "1") (pinfunction "IN_1") (pintype "passive"))
      (node (ref "J6") (pin "3") (pinfunction "IN_3") (pintype "passive"))
      (node (ref "J6") (pin "5") (pinfunction "IN_5") (pintype "passive"))
      (node (ref "X2") (pin "7") (pinfunction "7_7") (pintype "power_in"))
    )
    (net (code "63") (name "Net-(R4-Pad1)") (class "Default")
      (node (ref "R4") (pin "1") (pinfunction "1_1") (pintype "passive"))
      (node (ref "R6") (pin "1") (pinfunction "1_1") (pintype "passive"))
    )
    (net (code "64") (name "Net-(R5-Pad1)") (class "Default")
      (node (ref "R5") (pin "1") (pinfunction "1_1") (pintype "passive"))
      (node (ref "R7") (pin "1") (pinfunction "1_1") (pintype "passive"))
    )
    (net (code "65") (name "Net-(R18-Pad1)") (class "Default")
      (node (ref "R18") (pin "1") (pinfunction "1_1") (pintype "passive"))
      (node (ref "R19") (pin "1") (pinfunction "1_1") (pintype "passive"))
    )
    (net (code "66") (name "VCCIN") (class "Default")
      (node (ref "C20") (pin "2") (pinfunction "2_2") (pintype "passive"))
      (node (ref "C21") (pin "2") (pinfunction "2_2") (pintype "passive"))
      (node (ref "C22") (pin "1") (pinfunction "1_1") (pintype "passive"))
      (node (ref "C23") (pin "1") (pinfunction "1_1") (pintype "passive"))
      (node (ref "C24") (pin "2") (pinfunction "2_2") (pintype "passive"))
      (node (ref "C25") (pin "2") (pinfunction "2_2") (pintype "passive"))
      (node (ref "C29") (pin "2") (pinfunction "2_2") (pintype "passive"))
      (node (ref "C30") (pin "1") (pinfunction "1_1") (pintype "passive"))
      (node (ref "C31") (pin "2") (pinfunction "2_2") (pintype "passive"))
      (node (ref "D3") (pin "16") (pinfunction "VBB1_16") (pintype "passive"))
      (node (ref "D3") (pin "21") (pinfunction "VBB2_21") (pintype "passive"))
      (node (ref "D4") (pin "16") (pinfunction "VBB1_16") (pintype "passive"))
      (node (ref "D4") (pin "21") (pinfunction "VBB2_21") (pintype "passive"))
      (node (ref "D5") (pin "16") (pinfunction "VBB1_16") (pintype "passive"))
      (node (ref "D5") (pin "21") (pinfunction "VBB2_21") (pintype "passive"))
    )
  )
)
